# FPC_Jumper_Board.net
KiCad netlist of a schematic drawn in EAGLE
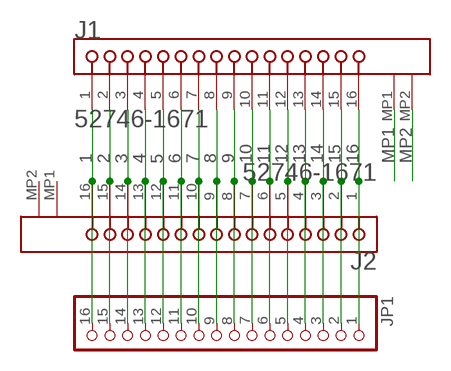
[diagram p0: schematic, sheet 1]

(export (version "E")
  (design (tool "Eeschema 10.0.6"))
  (components
    (comp (ref "J1")
      (value "MOLEX_52746-1671MOLEX_52746-1671_0_0")
      (footprint "eagle-import:MOLEX_52746-1671_0")
      (fields (field (name "MF") "Molex") (field (name "MPN") "52746-1671"))
      (libsource (lib "eagle-import") (part "MOLEX_52746-1671MOLEX_52746-1671_0_0"))
    )
    (comp (ref "J2")
      (value "MOLEX_52746-1671MOLEX_52746-1671_0_0")
      (footprint "eagle-import:MOLEX_52746-1671_0")
      (fields (field (name "MF") "Molex") (field (name "MPN") "52746-1671"))
      (libsource (lib "eagle-import") (part "MOLEX_52746-1671MOLEX_52746-1671_0_0"))
    )
    (comp (ref "JP1")
      (value "PINHD-1X16")
      (footprint "eagle-import:1X16")
      (libsource (lib "eagle-import") (part "PINHD-1X16"))
    )
  )
  (nets
    (net (code "1") (name "/1") (class "Default")
      (node (ref "J1") (pin "1") (pinfunction "1_1") (pintype "passive"))
      (node (ref "J2") (pin "16") (pinfunction "16_16") (pintype "passive"))
      (node (ref "JP1") (pin "16") (pinfunction "16_16") (pintype "passive"))
    )
    (net (code "2") (name "/2") (class "Default")
      (node (ref "J1") (pin "2") (pinfunction "2_2") (pintype "passive"))
      (node (ref "J2") (pin "15") (pinfunction "15_15") (pintype "passive"))
      (node (ref "JP1") (pin "15") (pinfunction "15_15") (pintype "passive"))
    )
    (net (code "3") (name "/3") (class "Default")
      (node (ref "J1") (pin "3") (pinfunction "3_3") (pintype "passive"))
      (node (ref "J2") (pin "14") (pinfunction "14_14") (pintype "passive"))
      (node (ref "JP1") (pin "14") (pinfunction "14_14") (pintype "passive"))
    )
    (net (code "4") (name "/4") (class "Default")
      (node (ref "J1") (pin "4") (pinfunction "4_4") (pintype "passive"))
      (node (ref "J2") (pin "13") (pinfunction "13_13") (pintype "passive"))
      (node (ref "JP1") (pin "13") (pinfunction "13_13") (pintype "passive"))
    )
    (net (code "5") (name "/5") (class "Default")
      (node (ref "J1") (pin "5") (pinfunction "5_5") (pintype "passive"))
      (node (ref "J2") (pin "12") (pinfunction "12_12") (pintype "passive"))
      (node (ref "JP1") (pin "12") (pinfunction "12_12") (pintype "passive"))
    )
    (net (code "6") (name "/6") (class "Default")
      (node (ref "J1") (pin "6") (pinfunction "6_6") (pintype "passive"))
      (node (ref "J2") (pin "11") (pinfunction "11_11") (pintype "passive"))
      (node (ref "JP1") (pin "11") (pinfunction "11_11") (pintype "passive"))
    )
    (net (code "7") (name "/7") (class "Default")
      (node (ref "J1") (pin "7") (pinfunction "7_7") (pintype "passive"))
      (node (ref "J2") (pin "10") (pinfunction "10_10") (pintype "passive"))
      (node (ref "JP1") (pin "10") (pinfunction "10_10") (pintype "passive"))
    )
    (net (code "8") (name "/8") (class "Default")
      (node (ref "J1") (pin "8") (pinfunction "8_8") (pintype "passive"))
      (node (ref "J2") (pin "9") (pinfunction "9_9") (pintype "passive"))
      (node (ref "JP1") (pin "9") (pinfunction "9_9") (pintype "passive"))
    )
    (net (code "9") (name "/9") (class "Default")
      (node (ref "J1") (pin "9") (pinfunction "9_9") (pintype "passive"))
      (node (ref "J2") (pin "8") (pinfunction "8_8") (pintype "passive"))
      (node (ref "JP1") (pin "8") (pinfunction "8_8") (pintype "passive"))
    )
    (net (code "10") (name "/10") (class "Default")
      (node (ref "J1") (pin "10") (pinfunction "10_10") (pintype "passive"))
      (node (ref "J2") (pin "7") (pinfunction "7_7") (pintype "passive"))
      (node (ref "JP1") (pin "7") (pinfunction "7_7") (pintype "passive"))
    )
    (net (code "11") (name "/11") (class "Default")
      (node (ref "J1") (pin "11") (pinfunction "11_11") (pintype "passive"))
      (node (ref "J2") (pin "6") (pinfunction "6_6") (pintype "passive"))
      (node (ref "JP1") (pin "6") (pinfunction "6_6") (pintype "passive"))
    )
    (net (code "12") (name "/12") (class "Default")
      (node (ref "J1") (pin "12") (pinfunction "12_12") (pintype "passive"))
      (node (ref "J2") (pin "5") (pinfunction "5_5") (pintype "passive"))
      (node (ref "JP1") (pin "5") (pinfunction "5_5") (pintype "passive"))
    )
    (net (code "13") (name "/13") (class "Default")
      (node (ref "J1") (pin "13") (pinfunction "13_13") (pintype "passive"))
      (node (ref "J2") (pin "4") (pinfunction "4_4") (pintype "passive"))
      (node (ref "JP1") (pin "4") (pinfunction "4_4") (pintype "passive"))
    )
    (net (code "14") (name "/14") (class "Default")
      (node (ref "J1") (pin "14") (pinfunction "14_14") (pintype "passive"))
      (node (ref "J2") (pin "3") (pinfunction "3_3") (pintype "passive"))
      (node (ref "JP1") (pin "3") (pinfunction "3_3") (pintype "passive"))
    )
    (net (code "15") (name "/15") (class "Default")
      (node (ref "J1") (pin "15") (pinfunction "15_15") (pintype "passive"))
      (node (ref "J2") (pin "2") (pinfunction "2_2") (pintype "passive"))
      (node (ref "JP1") (pin "2") (pinfunction "2_2") (pintype "passive"))
    )
    (net (code "16") (name "/16") (class "Default")
      (node (ref "J1") (pin "16") (pinfunction "16_16") (pintype "passive"))
      (node (ref "J2") (pin "1") (pinfunction "1_1") (pintype "passive"))
      (node (ref "JP1") (pin "1") (pinfunction "1_1") (pintype "passive"))
    )
    (net (code "17") (name "/MP1") (class "Default")
      (node (ref "J1") (pin "MP1") (pinfunction "MP1_MP1") (pintype "passive"))
    )
    (net (code "18") (name "/MP2") (class "Default")
      (node (ref "J1") (pin "MP2") (pinfunction "MP2_MP2") (pintype "passive"))
    )
    (net (code "19") (name "unconnected-(J2-PadMP1)") (class "Default")
      (node (ref "J2") (pin "MP1") (pinfunction "MP1_MP1") (pintype "passive"))
    )
    (net (code "20") (name "unconnected-(J2-PadMP2)") (class "Default")
      (node (ref "J2") (pin "MP2") (pinfunction "MP2_MP2") (pintype "passive"))
    )
  )
)
